# BT_Mate_MaKey.net
KiCad netlist of a schematic drawn in EAGLE
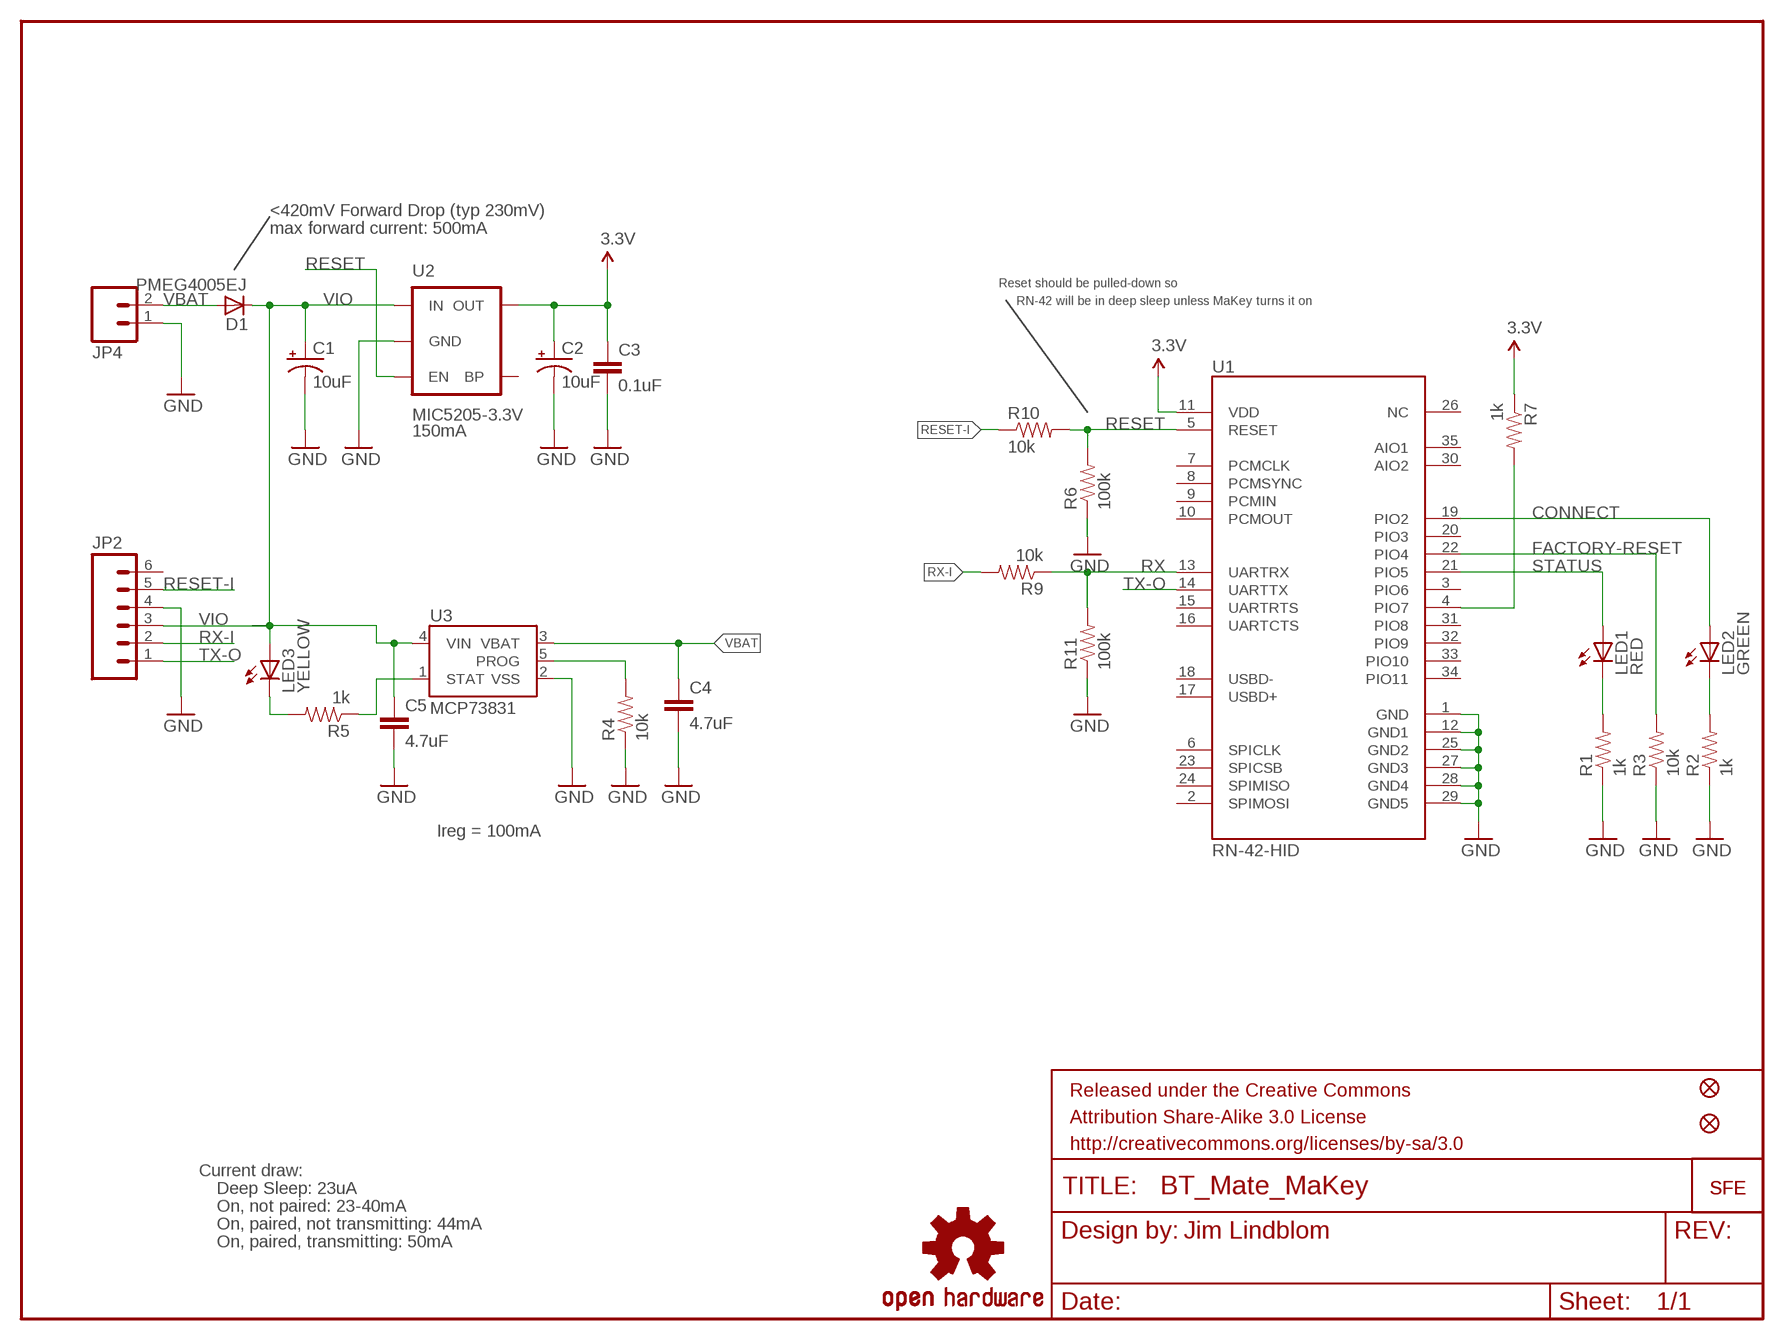
[diagram p0: schematic, sheet 1]

(export (version "E")
  (design (tool "Eeschema 10.0.6"))
  (components
    (comp (ref "C1")
      (value "10uF")
      (footprint "eagle-import:EIA3216")
      (libsource (lib "eagle-import") (part "CAP_POL1206"))
    )
    (comp (ref "C2")
      (value "10uF")
      (footprint "eagle-import:EIA3216")
      (libsource (lib "eagle-import") (part "CAP_POL1206"))
    )
    (comp (ref "C3")
      (value "0.1uF")
      (footprint "eagle-import:0402-CAP")
      (libsource (lib "eagle-import") (part "CAP0402-CAP"))
    )
    (comp (ref "C4")
      (value "4.7uF")
      (footprint "eagle-import:0402-CAP")
      (libsource (lib "eagle-import") (part "CAP0402-CAP"))
    )
    (comp (ref "C5")
      (value "4.7uF")
      (footprint "eagle-import:0402-CAP")
      (libsource (lib "eagle-import") (part "CAP0402-CAP"))
    )
    (comp (ref "D1")
      (value "PMEG4005EJ")
      (footprint "eagle-import:SOD-323")
      (libsource (lib "eagle-import") (part "DIODESOD"))
    )
    (comp (ref "JP1")
      (value "LOGO-SFESK")
      (footprint "eagle-import:SFE-LOGO-FLAME")
      (libsource (lib "eagle-import") (part "LOGO-SFESK"))
    )
    (comp (ref "JP2")
      (value "M06SIP")
      (footprint "eagle-import:1X06")
      (libsource (lib "eagle-import") (part "M06SIP"))
    )
    (comp (ref "JP3")
      (value "LOGO-SFENW2")
      (footprint "eagle-import:SFE-NEW-WEB")
      (libsource (lib "eagle-import") (part "LOGO-SFENW2"))
    )
    (comp (ref "JP4")
      (value "M02-JST-2MM-SMT")
      (footprint "eagle-import:JST-2-SMD")
      (libsource (lib "eagle-import") (part "M02-JST-2MM-SMT"))
    )
    (comp (ref "JP5")
      (value "FIDUCIALUFIDUCIAL")
      (footprint "eagle-import:MICRO-FIDUCIAL")
      (libsource (lib "eagle-import") (part "FIDUCIALUFIDUCIAL"))
    )
    (comp (ref "JP6")
      (value "FIDUCIALUFIDUCIAL")
      (footprint "eagle-import:MICRO-FIDUCIAL")
      (libsource (lib "eagle-import") (part "FIDUCIALUFIDUCIAL"))
    )
    (comp (ref "LED1")
      (value "RED")
      (footprint "eagle-import:LED-0603")
      (libsource (lib "eagle-import") (part "LED0603"))
    )
    (comp (ref "LED2")
      (value "GREEN")
      (footprint "eagle-import:LED-0603")
      (libsource (lib "eagle-import") (part "LED0603"))
    )
    (comp (ref "LED3")
      (value "YELLOW")
      (footprint "eagle-import:LED-0603")
      (libsource (lib "eagle-import") (part "LED0603"))
    )
    (comp (ref "R1")
      (value "1k")
      (footprint "eagle-import:0402-RES")
      (libsource (lib "eagle-import") (part "RESISTOR0402-RES"))
    )
    (comp (ref "R2")
      (value "1k")
      (footprint "eagle-import:0402-RES")
      (libsource (lib "eagle-import") (part "RESISTOR0402-RES"))
    )
    (comp (ref "R3")
      (value "10k")
      (footprint "eagle-import:0402-RES")
      (libsource (lib "eagle-import") (part "RESISTOR0402-RES"))
    )
    (comp (ref "R4")
      (value "10k")
      (footprint "eagle-import:0402-RES")
      (libsource (lib "eagle-import") (part "RESISTOR0402-RES"))
    )
    (comp (ref "R5")
      (value "1k")
      (footprint "eagle-import:0402-RES")
      (libsource (lib "eagle-import") (part "RESISTOR0402-RES"))
    )
    (comp (ref "R6")
      (value "100k")
      (footprint "eagle-import:0402-RES")
      (libsource (lib "eagle-import") (part "RESISTOR0402-RES"))
    )
    (comp (ref "R7")
      (value "1k")
      (footprint "eagle-import:0402-RES")
      (libsource (lib "eagle-import") (part "RESISTOR0402-RES"))
    )
    (comp (ref "R9")
      (value "10k")
      (footprint "eagle-import:0402-RES")
      (libsource (lib "eagle-import") (part "RESISTOR0402-RES"))
    )
    (comp (ref "R10")
      (value "10k")
      (footprint "eagle-import:0402-RES")
      (libsource (lib "eagle-import") (part "RESISTOR0402-RES"))
    )
    (comp (ref "R11")
      (value "100k")
      (footprint "eagle-import:0402-RES")
      (libsource (lib "eagle-import") (part "RESISTOR0402-RES"))
    )
    (comp (ref "U$2")
      (value "OSHW-LOGOS")
      (footprint "eagle-import:OSHW-LOGO-S")
      (libsource (lib "eagle-import") (part "OSHW-LOGOS"))
    )
    (comp (ref "U1")
      (value "RN-42-HID")
      (footprint "eagle-import:RN41")
      (libsource (lib "eagle-import") (part "BLUETOOTH-RN41{dblquote}"))
    )
    (comp (ref "U2")
      (value "MIC5205-3.3V")
      (footprint "eagle-import:SOT23-5")
      (libsource (lib "eagle-import") (part "V_REG_LDOSMD"))
    )
    (comp (ref "U3")
      (value "MCP73831")
      (footprint "eagle-import:SOT23-5")
      (libsource (lib "eagle-import") (part "MCP73831"))
    )
  )
  (nets
    (net (code "1") (name "/CONNECT") (class "Default")
      (node (ref "LED2") (pin "A") (pinfunction "A_A") (pintype "passive"))
      (node (ref "U1") (pin "19") (pinfunction "PIO2_19") (pintype "bidirectional"))
    )
    (net (code "2") (name "/FACTORY-RESET") (class "Default")
      (node (ref "R3") (pin "2") (pinfunction "2_2") (pintype "passive"))
      (node (ref "U1") (pin "22") (pinfunction "PIO4_22") (pintype "bidirectional"))
    )
    (net (code "3") (name "/RESET") (class "Default")
      (node (ref "R10") (pin "2") (pinfunction "2_2") (pintype "passive"))
      (node (ref "R6") (pin "2") (pinfunction "2_2") (pintype "passive"))
      (node (ref "U1") (pin "5") (pinfunction "RESET_5") (pintype "bidirectional"))
      (node (ref "U2") (pin "3") (pinfunction "EN_3") (pintype "input"))
    )
    (net (code "4") (name "/RX") (class "Default")
      (node (ref "R11") (pin "2") (pinfunction "2_2") (pintype "passive"))
      (node (ref "R9") (pin "1") (pinfunction "1_1") (pintype "passive"))
      (node (ref "U1") (pin "13") (pinfunction "UARTRX_13") (pintype "bidirectional"))
    )
    (net (code "5") (name "/STATUS") (class "Default")
      (node (ref "LED1") (pin "A") (pinfunction "A_A") (pintype "passive"))
      (node (ref "U1") (pin "21") (pinfunction "PIO5_21") (pintype "bidirectional"))
    )
    (net (code "6") (name "/TX-O") (class "Default")
      (node (ref "JP2") (pin "1") (pinfunction "1_1") (pintype "passive"))
      (node (ref "U1") (pin "14") (pinfunction "UARTTX_14") (pintype "bidirectional"))
    )
    (net (code "7") (name "/VIO") (class "Default")
      (node (ref "C1") (pin "A") (pinfunction "+_A") (pintype "passive"))
      (node (ref "C5") (pin "1") (pinfunction "1_1") (pintype "passive"))
      (node (ref "D1") (pin "1") (pinfunction "C_1") (pintype "passive"))
      (node (ref "JP2") (pin "3") (pinfunction "3_3") (pintype "passive"))
      (node (ref "LED3") (pin "A") (pinfunction "A_A") (pintype "passive"))
      (node (ref "U2") (pin "1") (pinfunction "IN_1") (pintype "input"))
      (node (ref "U3") (pin "4") (pinfunction "VIN_4") (pintype "power_in"))
    )
    (net (code "8") (name "3.3V") (class "Default")
      (node (ref "C2") (pin "A") (pinfunction "+_A") (pintype "passive"))
      (node (ref "C3") (pin "1") (pinfunction "1_1") (pintype "passive"))
      (node (ref "R7") (pin "1") (pinfunction "1_1") (pintype "passive"))
      (node (ref "U1") (pin "11") (pinfunction "VDD_11") (pintype "bidirectional"))
      (node (ref "U2") (pin "5") (pinfunction "OUT_5") (pintype "passive"))
    )
    (net (code "9") (name "GND") (class "Default")
      (node (ref "C1") (pin "C") (pinfunction "-_C") (pintype "passive"))
      (node (ref "C2") (pin "C") (pinfunction "-_C") (pintype "passive"))
      (node (ref "C3") (pin "2") (pinfunction "2_2") (pintype "passive"))
      (node (ref "C4") (pin "2") (pinfunction "2_2") (pintype "passive"))
      (node (ref "C5") (pin "2") (pinfunction "2_2") (pintype "passive"))
      (node (ref "JP2") (pin "4") (pinfunction "4_4") (pintype "passive"))
      (node (ref "JP4") (pin "1") (pinfunction "2_1") (pintype "passive"))
      (node (ref "R1") (pin "1") (pinfunction "1_1") (pintype "passive"))
      (node (ref "R11") (pin "1") (pinfunction "1_1") (pintype "passive"))
      (node (ref "R2") (pin "1") (pinfunction "1_1") (pintype "passive"))
      (node (ref "R3") (pin "1") (pinfunction "1_1") (pintype "passive"))
      (node (ref "R4") (pin "1") (pinfunction "1_1") (pintype "passive"))
      (node (ref "R6") (pin "1") (pinfunction "1_1") (pintype "passive"))
      (node (ref "U1") (pin "1") (pinfunction "GND_1") (pintype "bidirectional"))
      (node (ref "U1") (pin "12") (pinfunction "GND1_12") (pintype "bidirectional"))
      (node (ref "U1") (pin "25") (pinfunction "GND2_25") (pintype "bidirectional"))
      (node (ref "U1") (pin "27") (pinfunction "GND3_27") (pintype "bidirectional"))
      (node (ref "U1") (pin "28") (pinfunction "GND4_28") (pintype "bidirectional"))
      (node (ref "U1") (pin "29") (pinfunction "GND5_29") (pintype "bidirectional"))
      (node (ref "U2") (pin "2") (pinfunction "GND_2") (pintype "input"))
      (node (ref "U3") (pin "2") (pinfunction "VSS_2") (pintype "power_in"))
    )
    (net (code "10") (name "Net-(LED1-PadC)") (class "Default")
      (node (ref "LED1") (pin "C") (pinfunction "C_C") (pintype "passive"))
      (node (ref "R1") (pin "2") (pinfunction "2_2") (pintype "passive"))
    )
    (net (code "11") (name "Net-(LED2-PadC)") (class "Default")
      (node (ref "LED2") (pin "C") (pinfunction "C_C") (pintype "passive"))
      (node (ref "R2") (pin "2") (pinfunction "2_2") (pintype "passive"))
    )
    (net (code "12") (name "Net-(LED3-PadC)") (class "Default")
      (node (ref "LED3") (pin "C") (pinfunction "C_C") (pintype "passive"))
      (node (ref "R5") (pin "2") (pinfunction "2_2") (pintype "passive"))
    )
    (net (code "13") (name "Net-(U1-PIO7)") (class "Default")
      (node (ref "R7") (pin "2") (pinfunction "2_2") (pintype "passive"))
      (node (ref "U1") (pin "4") (pinfunction "PIO7_4") (pintype "bidirectional"))
    )
    (net (code "14") (name "Net-(U3-PROG)") (class "Default")
      (node (ref "R4") (pin "2") (pinfunction "2_2") (pintype "passive"))
      (node (ref "U3") (pin "5") (pinfunction "PROG_5") (pintype "input"))
    )
    (net (code "15") (name "Net-(U3-STAT)") (class "Default")
      (node (ref "R5") (pin "1") (pinfunction "1_1") (pintype "passive"))
      (node (ref "U3") (pin "1") (pinfunction "STAT_1") (pintype "output"))
    )
    (net (code "16") (name "RESET-I") (class "Default")
      (node (ref "JP2") (pin "5") (pinfunction "5_5") (pintype "passive"))
      (node (ref "R10") (pin "1") (pinfunction "1_1") (pintype "passive"))
    )
    (net (code "17") (name "RX-I") (class "Default")
      (node (ref "JP2") (pin "2") (pinfunction "2_2") (pintype "passive"))
      (node (ref "R9") (pin "2") (pinfunction "2_2") (pintype "passive"))
    )
    (net (code "18") (name "VBAT") (class "Default")
      (node (ref "C4") (pin "1") (pinfunction "1_1") (pintype "passive"))
      (node (ref "D1") (pin "2") (pinfunction "A_2") (pintype "passive"))
      (node (ref "JP4") (pin "2") (pinfunction "1_2") (pintype "passive"))
      (node (ref "U3") (pin "3") (pinfunction "VBAT_3") (pintype "power_in"))
    )
    (net (code "19") (name "unconnected-(JP2-Pad6)") (class "Default")
      (node (ref "JP2") (pin "6") (pinfunction "6_6") (pintype "passive"))
    )
    (net (code "20") (name "unconnected-(U1-AIO1-Pad35)") (class "Default")
      (node (ref "U1") (pin "35") (pinfunction "AIO1_35") (pintype "bidirectional"))
    )
    (net (code "21") (name "unconnected-(U1-AIO2-Pad30)") (class "Default")
      (node (ref "U1") (pin "30") (pinfunction "AIO2_30") (pintype "bidirectional"))
    )
    (net (code "22") (name "unconnected-(U1-NC-Pad26)") (class "Default")
      (node (ref "U1") (pin "26") (pinfunction "NC_26") (pintype "bidirectional"))
    )
    (net (code "23") (name "unconnected-(U1-PCMCLK-Pad7)") (class "Default")
      (node (ref "U1") (pin "7") (pinfunction "PCMCLK_7") (pintype "bidirectional"))
    )
    (net (code "24") (name "unconnected-(U1-PCMIN-Pad9)") (class "Default")
      (node (ref "U1") (pin "9") (pinfunction "PCMIN_9") (pintype "bidirectional"))
    )
    (net (code "25") (name "unconnected-(U1-PCMOUT-Pad10)") (class "Default")
      (node (ref "U1") (pin "10") (pinfunction "PCMOUT_10") (pintype "bidirectional"))
    )
    (net (code "26") (name "unconnected-(U1-PCMSYNC-Pad8)") (class "Default")
      (node (ref "U1") (pin "8") (pinfunction "PCMSYNC_8") (pintype "bidirectional"))
    )
    (net (code "27") (name "unconnected-(U1-PIO3-Pad20)") (class "Default")
      (node (ref "U1") (pin "20") (pinfunction "PIO3_20") (pintype "bidirectional"))
    )
    (net (code "28") (name "unconnected-(U1-PIO6-Pad3)") (class "Default")
      (node (ref "U1") (pin "3") (pinfunction "PIO6_3") (pintype "bidirectional"))
    )
    (net (code "29") (name "unconnected-(U1-PIO8-Pad31)") (class "Default")
      (node (ref "U1") (pin "31") (pinfunction "PIO8_31") (pintype "bidirectional"))
    )
    (net (code "30") (name "unconnected-(U1-PIO9-Pad32)") (class "Default")
      (node (ref "U1") (pin "32") (pinfunction "PIO9_32") (pintype "bidirectional"))
    )
    (net (code "31") (name "unconnected-(U1-PIO10-Pad33)") (class "Default")
      (node (ref "U1") (pin "33") (pinfunction "PIO10_33") (pintype "bidirectional"))
    )
    (net (code "32") (name "unconnected-(U1-PIO11-Pad34)") (class "Default")
      (node (ref "U1") (pin "34") (pinfunction "PIO11_34") (pintype "bidirectional"))
    )
    (net (code "33") (name "unconnected-(U1-SPICLK-Pad6)") (class "Default")
      (node (ref "U1") (pin "6") (pinfunction "SPICLK_6") (pintype "bidirectional"))
    )
    (net (code "34") (name "unconnected-(U1-SPICSB-Pad23)") (class "Default")
      (node (ref "U1") (pin "23") (pinfunction "SPICSB_23") (pintype "bidirectional"))
    )
    (net (code "35") (name "unconnected-(U1-SPIMISO-Pad24)") (class "Default")
      (node (ref "U1") (pin "24") (pinfunction "SPIMISO_24") (pintype "bidirectional"))
    )
    (net (code "36") (name "unconnected-(U1-SPIMOSI-Pad2)") (class "Default")
      (node (ref "U1") (pin "2") (pinfunction "SPIMOSI_2") (pintype "bidirectional"))
    )
    (net (code "37") (name "unconnected-(U1-UARTCTS-Pad16)") (class "Default")
      (node (ref "U1") (pin "16") (pinfunction "UARTCTS_16") (pintype "bidirectional"))
    )
    (net (code "38") (name "unconnected-(U1-UARTRTS-Pad15)") (class "Default")
      (node (ref "U1") (pin "15") (pinfunction "UARTRTS_15") (pintype "bidirectional"))
    )
    (net (code "39") (name "unconnected-(U1-USBD+-Pad17)") (class "Default")
      (node (ref "U1") (pin "17") (pinfunction "USBD+_17") (pintype "bidirectional"))
    )
    (net (code "40") (name "unconnected-(U1-USBD--Pad18)") (class "Default")
      (node (ref "U1") (pin "18") (pinfunction "USBD-_18") (pintype "bidirectional"))
    )
    (net (code "41") (name "unconnected-(U2-BP-Pad4)") (class "Default")
      (node (ref "U2") (pin "4") (pinfunction "BP_4") (pintype "input"))
    )
  )
)
